# Alim_Ticketing_Master.net
KiCad netlist of a schematic drawn in Altium Designer
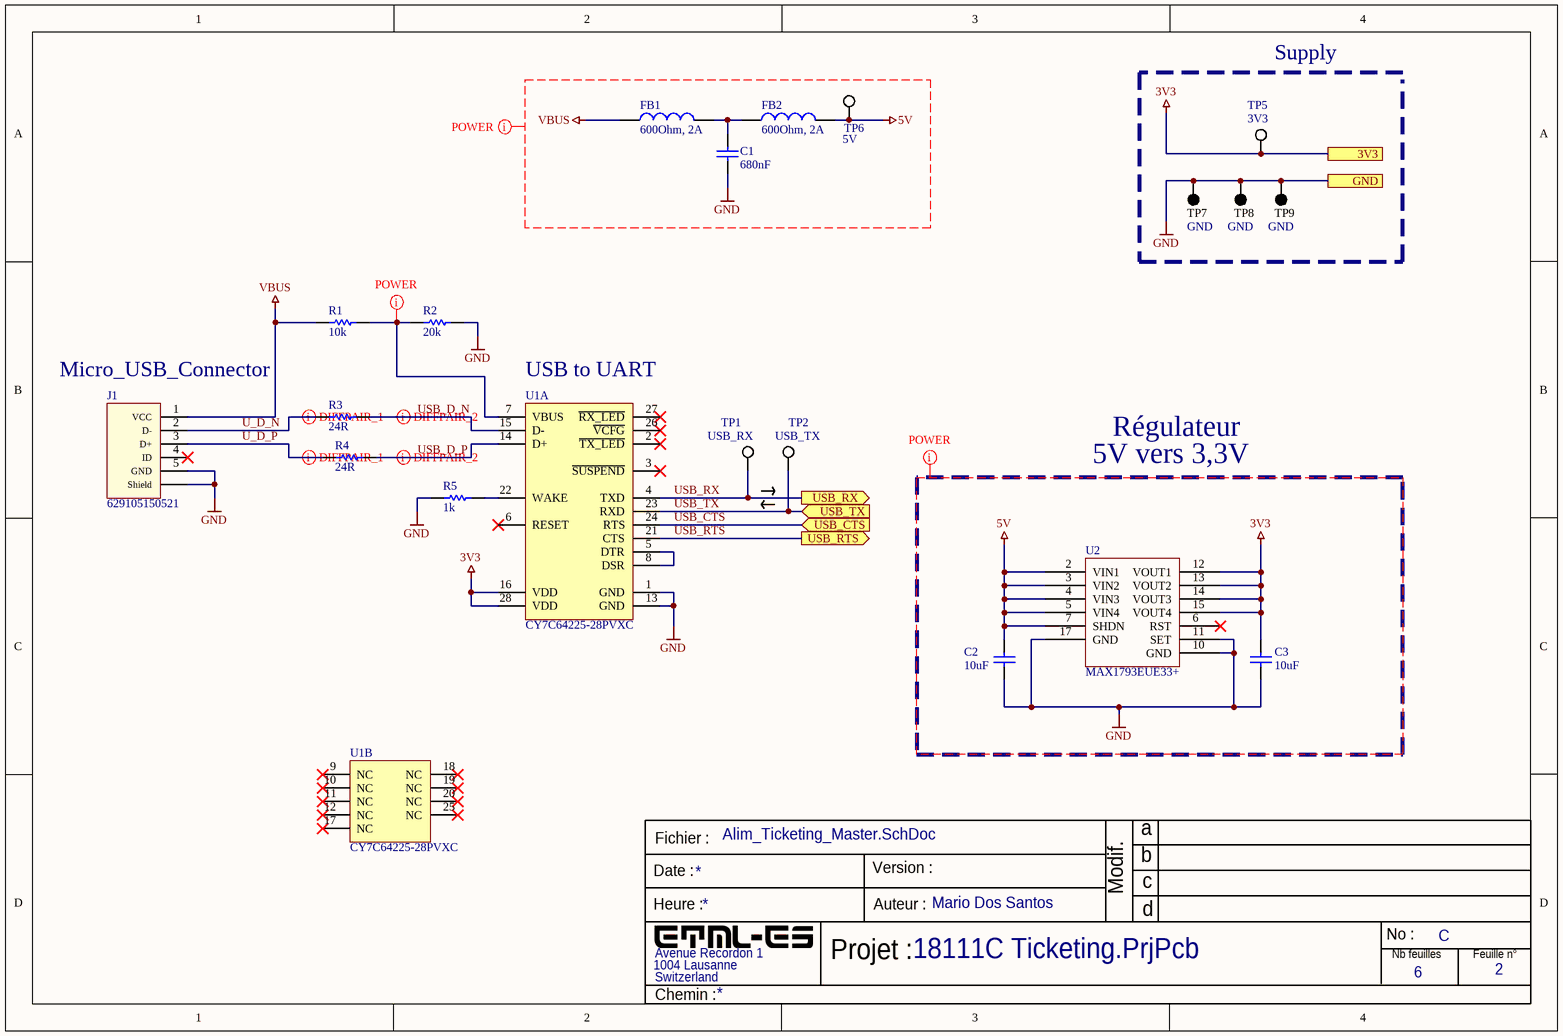
[diagram p0: Alim_Ticketing_Master.SchDoc]

(export (version "E")
  (design (tool "Eeschema 10.0.6"))
  (components
    (comp (ref "C1")
      (value "680nF")
      (footprint "6-0805_N")
      (description "WCAP-CSGP General Purpose Ceramic Capacitors, size 0805, 100nF, +/-10%, 50VDC")
      (libsource (lib "VPA_v2b") (part "885012207098"))
    )
    (comp (ref "C2")
      (value "10uF")
      (footprint "6-0805_N")
      (description "Capacitor")
      (fields (field (name "PUBLISHER") "Altium Limited"))
      (libsource (lib "Miscellaneous Devices") (part "Cap"))
    )
    (comp (ref "C3")
      (value "10uF")
      (footprint "6-0805_N")
      (description "Capacitor")
      (fields (field (name "PUBLISHER") "Altium Limited"))
      (libsource (lib "Miscellaneous Devices") (part "Cap"))
    )
    (comp (ref "FB1")
      (value "600Ohm, 2A")
      (footprint "WE-CBF_0805_High Current")
      (description "WE-CBF SMT EMI Suppression Ferrite Bead, size 0805, 600Ohm, 2A")
      (fields (field (name "PART NUMBER") "742792040") (field (name "PUBLISHER") "Wurth Elektronik"))
      (libsource (lib "VPA_v2b") (part "742792040"))
    )
    (comp (ref "FB2")
      (value "600Ohm, 2A")
      (footprint "WE-CBF_0805_High Current")
      (description "WE-CBF SMT EMI Suppression Ferrite Bead, size 0805, 600Ohm, 2A")
      (fields (field (name "PART NUMBER") "742792040") (field (name "PUBLISHER") "Wurth Elektronik"))
      (libsource (lib "VPA_v2b") (part "742792040"))
    )
    (comp (ref "J1")
      (value "629105150521")
      (footprint "629105150521")
      (description "Micro USB 2.0 SMT Type B Horizontal 5 Contacts High Current WR-COM")
      (fields (field (name "PART NUMBER") "732-5960-1-ND") (field (name "PUBLISHER") "Wurth Elektronik"))
      (libsource (lib "PCB_Ticketing_Slave") (part "629105150521"))
    )
    (comp (ref "R1")
      (value "10k")
      (footprint "RESC0805(2012)_L")
      (description "100K 0.125W 5% 0805 (2012 Metric)  SMD")
      (fields (field (name "TOLERANCE") "5 %") (field (name "POWER") "0.125 W"))
      (libsource (lib "Altium Content Vault") (part "CMP-1013-00122-1"))
    )
    (comp (ref "R2")
      (value "20k")
      (footprint "RESC0805(2012)_L")
      (description "100K 0.125W 5% 0805 (2012 Metric)  SMD")
      (fields (field (name "TOLERANCE") "5 %") (field (name "POWER") "0.125 W"))
      (libsource (lib "Altium Content Vault") (part "CMP-1013-00122-1"))
    )
    (comp (ref "R3")
      (value "24R")
      (footprint "RESC0805(2012)_L")
      (description "100K 0.125W 5% 0805 (2012 Metric)  SMD")
      (fields (field (name "TOLERANCE") "5 %") (field (name "POWER") "0.125 W"))
      (libsource (lib "Altium Content Vault") (part "CMP-1013-00122-1"))
    )
    (comp (ref "R4")
      (value "24R")
      (footprint "RESC0805(2012)_L")
      (description "100K 0.125W 5% 0805 (2012 Metric)  SMD")
      (fields (field (name "TOLERANCE") "5 %") (field (name "POWER") "0.125 W"))
      (libsource (lib "Altium Content Vault") (part "CMP-1013-00122-1"))
    )
    (comp (ref "R5")
      (value "1k")
      (footprint "RESC0805(2012)_L")
      (description "100K 0.125W 5% 0805 (2012 Metric)  SMD")
      (fields (field (name "TOLERANCE") "5 %") (field (name "POWER") "0.125 W"))
      (libsource (lib "Altium Content Vault") (part "CMP-1013-00122-1"))
    )
    (comp (ref "TP1")
      (value "~")
      (footprint "KSTN-5019_V")
      (description "Test Point, 1 Position SMD, RoHS, Tape and Reel")
      (libsource (lib "Altium Content Vault") (part "TESTPOINT_WHITE"))
    )
    (comp (ref "TP2")
      (value "~")
      (footprint "KSTN-5019_V")
      (description "Test Point, 1 Position SMD, RoHS, Tape and Reel")
      (libsource (lib "Altium Content Vault") (part "TESTPOINT_WHITE"))
    )
    (comp (ref "TP5")
      (value "~")
      (footprint "KSTN-5019_V")
      (description "Test Point, 1 Position SMD, RoHS, Tape and Reel")
      (libsource (lib "Altium Content Vault") (part "TESTPOINT_WHITE"))
    )
    (comp (ref "TP6")
      (value "~")
      (footprint "KSTN-5019_V")
      (description "Test Point, 1 Position SMD, RoHS, Tape and Reel")
      (libsource (lib "Altium Content Vault") (part "TESTPOINT_WHITE"))
    )
    (comp (ref "TP7")
      (value "~")
      (footprint "KSTN-5011_V")
      (description "Test Point, Black, Through Hole, RoHS, Bulk,5011")
      (fields (field (name "MANUFACTURER") "Keystone"))
      (libsource (lib "Altium Content Vault") (part "TESTPOINT_BLACK"))
    )
    (comp (ref "TP8")
      (value "~")
      (footprint "KSTN-5011_V")
      (description "Test Point, Black, Through Hole, RoHS, Bulk,5011")
      (fields (field (name "MANUFACTURER") "Keystone"))
      (libsource (lib "Altium Content Vault") (part "TESTPOINT_BLACK"))
    )
    (comp (ref "TP9")
      (value "~")
      (footprint "KSTN-5011_V")
      (description "Test Point, Black, Through Hole, RoHS, Bulk,5011")
      (fields (field (name "MANUFACTURER") "Keystone"))
      (libsource (lib "Altium Content Vault") (part "TESTPOINT_BLACK"))
    )
    (comp (ref "U1")
      (value "CY7C64225-28PVXC")
      (footprint "CYP-PVX28_N")
      (description "USB-to-UART Bridge Controller, 3 to 5.25 V, 0 to 70 degC, 28-Pin SSOP (PVX28), Tube")
      (fields (field (name "MANUFACTURER") "Cypress") (field (name "PART NUMBER") "428-3158-ND"))
      (libsource (lib "PCB_Ticketing_Slave") (part "CMP-0967-00143-1"))
    )
    (comp (ref "U2")
      (value "MAX1793EUE33+")
      (footprint "TSOP65P640X110_HS-17N")
      (libsource (lib "2018A_CarteIoEscapeRoom_CAD") (part "MAX1793"))
    )
  )
  (nets
    (net (code "1") (name "/USB_CTS") (class "Default")
      (node (ref "U1") (pin "24") (pinfunction "RTS_24") (pintype "passive"))
    )
    (net (code "2") (name "/USB_D_N") (class "Default")
      (node (ref "R3") (pin "2") (pinfunction "2_2") (pintype "passive"))
      (node (ref "U1") (pin "15") (pinfunction "D-_15") (pintype "passive"))
    )
    (net (code "3") (name "/USB_D_P") (class "Default")
      (node (ref "R4") (pin "2") (pinfunction "2_2") (pintype "passive"))
      (node (ref "U1") (pin "14") (pinfunction "D+_14") (pintype "passive"))
    )
    (net (code "4") (name "/USB_RTS") (class "Default")
      (node (ref "U1") (pin "21") (pinfunction "CTS_21") (pintype "passive"))
    )
    (net (code "5") (name "/USB_RX") (class "Default")
      (node (ref "TP1") (pin "1") (pinfunction "1_1") (pintype "passive"))
      (node (ref "U1") (pin "4") (pinfunction "TXD_4") (pintype "passive"))
    )
    (net (code "6") (name "/USB_TX") (class "Default")
      (node (ref "TP2") (pin "1") (pinfunction "1_1") (pintype "passive"))
      (node (ref "U1") (pin "23") (pinfunction "RXD_23") (pintype "passive"))
    )
    (net (code "7") (name "/U_D_N") (class "Default")
      (node (ref "J1") (pin "2") (pinfunction "D-_2") (pintype "passive"))
      (node (ref "R3") (pin "1") (pinfunction "1_1") (pintype "passive"))
    )
    (net (code "8") (name "/U_D_P") (class "Default")
      (node (ref "J1") (pin "3") (pinfunction "D+_3") (pintype "passive"))
      (node (ref "R4") (pin "1") (pinfunction "1_1") (pintype "passive"))
    )
    (net (code "9") (name "3V3") (class "Default")
      (node (ref "C3") (pin "2") (pinfunction "2_2") (pintype "passive"))
      (node (ref "TP5") (pin "1") (pinfunction "1_1") (pintype "passive"))
      (node (ref "U1") (pin "16") (pinfunction "VDD_16") (pintype "passive"))
      (node (ref "U1") (pin "28") (pinfunction "VDD_28") (pintype "passive"))
      (node (ref "U2") (pin "12") (pinfunction "VOUT1_12") (pintype "passive"))
      (node (ref "U2") (pin "13") (pinfunction "VOUT2_13") (pintype "passive"))
      (node (ref "U2") (pin "14") (pinfunction "VOUT3_14") (pintype "passive"))
      (node (ref "U2") (pin "15") (pinfunction "VOUT4_15") (pintype "passive"))
    )
    (net (code "10") (name "5V") (class "Default")
      (node (ref "C2") (pin "1") (pinfunction "1_1") (pintype "passive"))
      (node (ref "FB2") (pin "2") (pinfunction "2_2") (pintype "passive"))
      (node (ref "TP6") (pin "1") (pinfunction "1_1") (pintype "passive"))
      (node (ref "U2") (pin "2") (pinfunction "VIN1_2") (pintype "passive"))
      (node (ref "U2") (pin "3") (pinfunction "VIN2_3") (pintype "passive"))
      (node (ref "U2") (pin "4") (pinfunction "VIN3_4") (pintype "passive"))
      (node (ref "U2") (pin "5") (pinfunction "VIN4_5") (pintype "passive"))
      (node (ref "U2") (pin "7") (pinfunction "SHDN_7") (pintype "passive"))
    )
    (net (code "11") (name "GND") (class "Default")
      (node (ref "C1") (pin "2") (pinfunction "2_2") (pintype "passive"))
      (node (ref "C2") (pin "2") (pinfunction "2_2") (pintype "passive"))
      (node (ref "C3") (pin "1") (pinfunction "1_1") (pintype "passive"))
      (node (ref "J1") (pin "5") (pinfunction "GND_5") (pintype "passive"))
      (node (ref "J1") (pin "Shell") (pinfunction "Shield_Shell") (pintype "passive"))
      (node (ref "R2") (pin "2") (pinfunction "2_2") (pintype "passive"))
      (node (ref "R5") (pin "2") (pinfunction "2_2") (pintype "passive"))
      (node (ref "TP7") (pin "1") (pinfunction "1_1") (pintype "passive"))
      (node (ref "TP8") (pin "1") (pinfunction "1_1") (pintype "passive"))
      (node (ref "TP9") (pin "1") (pinfunction "1_1") (pintype "passive"))
      (node (ref "U1") (pin "1") (pinfunction "GND_1") (pintype "passive"))
      (node (ref "U1") (pin "13") (pinfunction "GND_13") (pintype "passive"))
      (node (ref "U2") (pin "10") (pinfunction "GND_10") (pintype "power_in"))
      (node (ref "U2") (pin "11") (pinfunction "SET_11") (pintype "passive"))
      (node (ref "U2") (pin "17") (pinfunction "GND_17") (pintype "power_in"))
    )
    (net (code "12") (name "Net-(C1-Pad1)") (class "Default")
      (node (ref "C1") (pin "1") (pinfunction "1_1") (pintype "passive"))
      (node (ref "FB1") (pin "2") (pinfunction "2_2") (pintype "passive"))
      (node (ref "FB2") (pin "1") (pinfunction "1_1") (pintype "passive"))
    )
    (net (code "13") (name "Net-(U1A-DSR)") (class "Default")
      (node (ref "U1") (pin "5") (pinfunction "DTR_5") (pintype "passive"))
      (node (ref "U1") (pin "8") (pinfunction "DSR_8") (pintype "passive"))
    )
    (net (code "14") (name "Net-(U1A-VBUS)") (class "Default")
      (node (ref "R1") (pin "2") (pinfunction "2_2") (pintype "passive"))
      (node (ref "R2") (pin "1") (pinfunction "1_1") (pintype "passive"))
      (node (ref "U1") (pin "7") (pinfunction "VBUS_7") (pintype "passive"))
    )
    (net (code "15") (name "Net-(U1A-WAKE)") (class "Default")
      (node (ref "R5") (pin "1") (pinfunction "1_1") (pintype "passive"))
      (node (ref "U1") (pin "22") (pinfunction "WAKE_22") (pintype "passive"))
    )
    (net (code "16") (name "VBUS") (class "Default")
      (node (ref "FB1") (pin "1") (pinfunction "1_1") (pintype "passive"))
      (node (ref "J1") (pin "1") (pinfunction "VCC_1") (pintype "passive"))
      (node (ref "R1") (pin "1") (pinfunction "1_1") (pintype "passive"))
    )
    (net (code "17") (name "unconnected-(J1-ID-Pad4)") (class "Default")
      (node (ref "J1") (pin "4") (pinfunction "ID_4") (pintype "passive+no_connect"))
    )
    (net (code "18") (name "unconnected-(U1A-RESET-Pad6)") (class "Default")
      (node (ref "U1") (pin "6") (pinfunction "RESET_6") (pintype "passive+no_connect"))
    )
    (net (code "19") (name "unconnected-(U1A-~{RX_LED}-Pad27)") (class "Default")
      (node (ref "U1") (pin "27") (pinfunction "~{RX_LED}_27") (pintype "passive+no_connect"))
    )
    (net (code "20") (name "unconnected-(U1A-~{SUSPEND}-Pad3)") (class "Default")
      (node (ref "U1") (pin "3") (pinfunction "~{SUSPEND}_3") (pintype "passive+no_connect"))
    )
    (net (code "21") (name "unconnected-(U1A-~{TX_LED}-Pad2)") (class "Default")
      (node (ref "U1") (pin "2") (pinfunction "~{TX_LED}_2") (pintype "passive+no_connect"))
    )
    (net (code "22") (name "unconnected-(U1A-~{VCFG}-Pad26)") (class "Default")
      (node (ref "U1") (pin "26") (pinfunction "~{VCFG}_26") (pintype "passive+no_connect"))
    )
    (net (code "23") (name "unconnected-(U1B-NC-Pad9)") (class "Default")
      (node (ref "U1") (pin "9") (pinfunction "NC_9") (pintype "passive+no_connect"))
    )
    (net (code "24") (name "unconnected-(U1B-NC-Pad10)") (class "Default")
      (node (ref "U1") (pin "10") (pinfunction "NC_10") (pintype "passive+no_connect"))
    )
    (net (code "25") (name "unconnected-(U1B-NC-Pad11)") (class "Default")
      (node (ref "U1") (pin "11") (pinfunction "NC_11") (pintype "passive+no_connect"))
    )
    (net (code "26") (name "unconnected-(U1B-NC-Pad12)") (class "Default")
      (node (ref "U1") (pin "12") (pinfunction "NC_12") (pintype "passive+no_connect"))
    )
    (net (code "27") (name "unconnected-(U1B-NC-Pad17)") (class "Default")
      (node (ref "U1") (pin "17") (pinfunction "NC_17") (pintype "passive+no_connect"))
    )
    (net (code "28") (name "unconnected-(U1B-NC-Pad18)") (class "Default")
      (node (ref "U1") (pin "18") (pinfunction "NC_18") (pintype "passive+no_connect"))
    )
    (net (code "29") (name "unconnected-(U1B-NC-Pad19)") (class "Default")
      (node (ref "U1") (pin "19") (pinfunction "NC_19") (pintype "passive+no_connect"))
    )
    (net (code "30") (name "unconnected-(U1B-NC-Pad20)") (class "Default")
      (node (ref "U1") (pin "20") (pinfunction "NC_20") (pintype "passive+no_connect"))
    )
    (net (code "31") (name "unconnected-(U1B-NC-Pad25)") (class "Default")
      (node (ref "U1") (pin "25") (pinfunction "NC_25") (pintype "passive+no_connect"))
    )
    (net (code "32") (name "unconnected-(U2-RST-Pad6)") (class "Default")
      (node (ref "U2") (pin "6") (pinfunction "RST_6") (pintype "passive+no_connect"))
    )
  )
)
